# IotaWatt.net
KiCad netlist of a schematic drawn in EAGLE
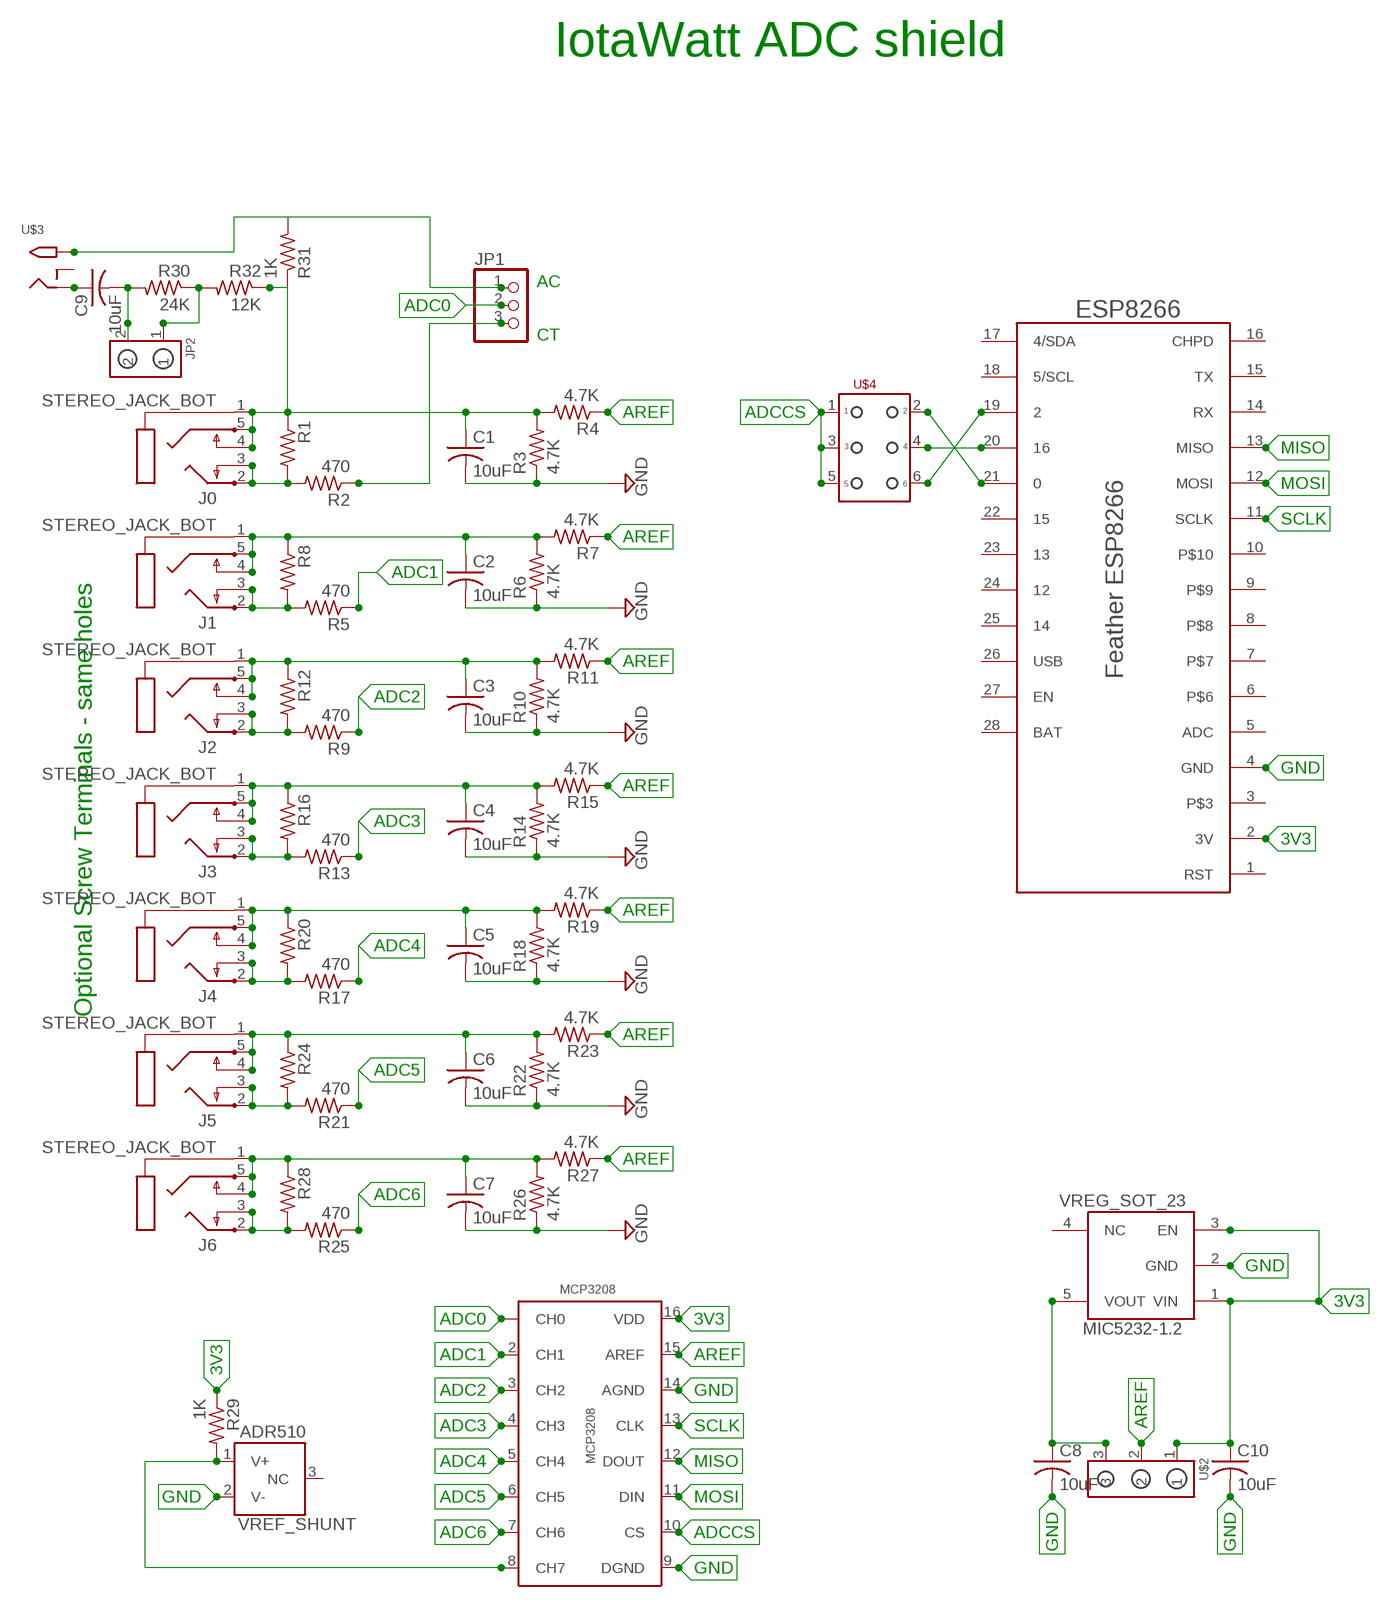
[diagram p0: schematic, sheet 1]

(export (version "E")
  (design (tool "Eeschema 10.0.6"))
  (components
    (comp (ref "ADR510")
      (value "VREF_SHUNT")
      (footprint "eagle-import:SOT23_3")
      (libsource (lib "eagle-import") (part "VREF_SHUNT"))
    )
    (comp (ref "C1")
      (value "10uF")
      (footprint "eagle-import:C0805")
      (libsource (lib "eagle-import") (part "C-USC0805"))
    )
    (comp (ref "C2")
      (value "10uF")
      (footprint "eagle-import:C0805")
      (libsource (lib "eagle-import") (part "C-USC0805"))
    )
    (comp (ref "C3")
      (value "10uF")
      (footprint "eagle-import:C0805")
      (libsource (lib "eagle-import") (part "C-USC0805"))
    )
    (comp (ref "C4")
      (value "10uF")
      (footprint "eagle-import:C0805")
      (libsource (lib "eagle-import") (part "C-USC0805"))
    )
    (comp (ref "C5")
      (value "10uF")
      (footprint "eagle-import:C0805")
      (libsource (lib "eagle-import") (part "C-USC0805"))
    )
    (comp (ref "C6")
      (value "10uF")
      (footprint "eagle-import:C0805")
      (libsource (lib "eagle-import") (part "C-USC0805"))
    )
    (comp (ref "C7")
      (value "10uF")
      (footprint "eagle-import:C0805")
      (libsource (lib "eagle-import") (part "C-USC0805"))
    )
    (comp (ref "C8")
      (value "10uF")
      (footprint "eagle-import:C0805")
      (libsource (lib "eagle-import") (part "C-USC0805"))
    )
    (comp (ref "C9")
      (value "10uF")
      (footprint "eagle-import:C0805")
      (libsource (lib "eagle-import") (part "C-USC0805"))
    )
    (comp (ref "C10")
      (value "10uF")
      (footprint "eagle-import:C0805")
      (libsource (lib "eagle-import") (part "C-USC0805"))
    )
    (comp (ref "J0")
      (value "STEREO_JACK_BOT")
      (footprint "eagle-import:STX3100")
      (libsource (lib "eagle-import") (part "STEREO_JACK_BOT"))
    )
    (comp (ref "J1")
      (value "STEREO_JACK_BOT")
      (footprint "eagle-import:STX3100")
      (libsource (lib "eagle-import") (part "STEREO_JACK_BOT"))
    )
    (comp (ref "J2")
      (value "STEREO_JACK_BOT")
      (footprint "eagle-import:STX3100")
      (libsource (lib "eagle-import") (part "STEREO_JACK_BOT"))
    )
    (comp (ref "J3")
      (value "STEREO_JACK_BOT")
      (footprint "eagle-import:STX3100")
      (libsource (lib "eagle-import") (part "STEREO_JACK_BOT"))
    )
    (comp (ref "J4")
      (value "STEREO_JACK_BOT")
      (footprint "eagle-import:STX3100")
      (libsource (lib "eagle-import") (part "STEREO_JACK_BOT"))
    )
    (comp (ref "J5")
      (value "STEREO_JACK_BOT")
      (footprint "eagle-import:STX3100")
      (libsource (lib "eagle-import") (part "STEREO_JACK_BOT"))
    )
    (comp (ref "J6")
      (value "STEREO_JACK_BOT")
      (footprint "eagle-import:STX3100")
      (libsource (lib "eagle-import") (part "STEREO_JACK_BOT"))
    )
    (comp (ref "JP1")
      (value "PINHD-1X3")
      (footprint "eagle-import:1X03")
      (libsource (lib "eagle-import") (part "PINHD-1X3"))
    )
    (comp (ref "JP2")
      (value "HEADER_1X2")
      (footprint "eagle-import:HEADER_1X2")
      (libsource (lib "eagle-import") (part "HEADER_1X2"))
    )
    (comp (ref "MCP3208")
      (value "MCP3208")
      (footprint "eagle-import:SOIC_16")
      (libsource (lib "eagle-import") (part "MCP3208"))
    )
    (comp (ref "MIC5232-1.2")
      (value "VREG_SOT_23")
      (footprint "eagle-import:SOT23_5")
      (libsource (lib "eagle-import") (part "VREG_SOT_23"))
    )
    (comp (ref "R1")
      (value "R-US_FLIPFLOP7")
      (footprint "eagle-import:0805-THM-7")
      (libsource (lib "eagle-import") (part "R-US_FLIPFLOP7"))
    )
    (comp (ref "R2")
      (value "470")
      (footprint "eagle-import:R0805")
      (libsource (lib "eagle-import") (part "R-US_R0805"))
    )
    (comp (ref "R3")
      (value "4.7K")
      (footprint "eagle-import:R0805")
      (libsource (lib "eagle-import") (part "R-US_R0805"))
    )
    (comp (ref "R4")
      (value "4.7K")
      (footprint "eagle-import:R0805")
      (libsource (lib "eagle-import") (part "R-US_R0805"))
    )
    (comp (ref "R5")
      (value "470")
      (footprint "eagle-import:R0805")
      (libsource (lib "eagle-import") (part "R-US_R0805"))
    )
    (comp (ref "R6")
      (value "4.7K")
      (footprint "eagle-import:R0805")
      (libsource (lib "eagle-import") (part "R-US_R0805"))
    )
    (comp (ref "R7")
      (value "4.7K")
      (footprint "eagle-import:R0805")
      (libsource (lib "eagle-import") (part "R-US_R0805"))
    )
    (comp (ref "R8")
      (value "R-US_FLIPFLOP7")
      (footprint "eagle-import:0805-THM-7")
      (libsource (lib "eagle-import") (part "R-US_FLIPFLOP7"))
    )
    (comp (ref "R9")
      (value "470")
      (footprint "eagle-import:R0805")
      (libsource (lib "eagle-import") (part "R-US_R0805"))
    )
    (comp (ref "R10")
      (value "4.7K")
      (footprint "eagle-import:R0805")
      (libsource (lib "eagle-import") (part "R-US_R0805"))
    )
    (comp (ref "R11")
      (value "4.7K")
      (footprint "eagle-import:R0805")
      (libsource (lib "eagle-import") (part "R-US_R0805"))
    )
    (comp (ref "R12")
      (value "R-US_FLIPFLOP7")
      (footprint "eagle-import:0805-THM-7")
      (libsource (lib "eagle-import") (part "R-US_FLIPFLOP7"))
    )
    (comp (ref "R13")
      (value "470")
      (footprint "eagle-import:R0805")
      (libsource (lib "eagle-import") (part "R-US_R0805"))
    )
    (comp (ref "R14")
      (value "4.7K")
      (footprint "eagle-import:R0805")
      (libsource (lib "eagle-import") (part "R-US_R0805"))
    )
    (comp (ref "R15")
      (value "4.7K")
      (footprint "eagle-import:R0805")
      (libsource (lib "eagle-import") (part "R-US_R0805"))
    )
    (comp (ref "R16")
      (value "R-US_FLIPFLOP7")
      (footprint "eagle-import:0805-THM-7")
      (libsource (lib "eagle-import") (part "R-US_FLIPFLOP7"))
    )
    (comp (ref "R17")
      (value "470")
      (footprint "eagle-import:R0805")
      (libsource (lib "eagle-import") (part "R-US_R0805"))
    )
    (comp (ref "R18")
      (value "4.7K")
      (footprint "eagle-import:R0805")
      (libsource (lib "eagle-import") (part "R-US_R0805"))
    )
    (comp (ref "R19")
      (value "4.7K")
      (footprint "eagle-import:R0805")
      (libsource (lib "eagle-import") (part "R-US_R0805"))
    )
    (comp (ref "R20")
      (value "R-US_FLIPFLOP7")
      (footprint "eagle-import:0805-THM-7")
      (libsource (lib "eagle-import") (part "R-US_FLIPFLOP7"))
    )
    (comp (ref "R21")
      (value "470")
      (footprint "eagle-import:R0805")
      (libsource (lib "eagle-import") (part "R-US_R0805"))
    )
    (comp (ref "R22")
      (value "4.7K")
      (footprint "eagle-import:R0805")
      (libsource (lib "eagle-import") (part "R-US_R0805"))
    )
    (comp (ref "R23")
      (value "4.7K")
      (footprint "eagle-import:R0805")
      (libsource (lib "eagle-import") (part "R-US_R0805"))
    )
    (comp (ref "R24")
      (value "R-US_FLIPFLOP7")
      (footprint "eagle-import:0805-THM-7")
      (libsource (lib "eagle-import") (part "R-US_FLIPFLOP7"))
    )
    (comp (ref "R25")
      (value "470")
      (footprint "eagle-import:R0805")
      (libsource (lib "eagle-import") (part "R-US_R0805"))
    )
    (comp (ref "R26")
      (value "4.7K")
      (footprint "eagle-import:R0805")
      (libsource (lib "eagle-import") (part "R-US_R0805"))
    )
    (comp (ref "R27")
      (value "4.7K")
      (footprint "eagle-import:R0805")
      (libsource (lib "eagle-import") (part "R-US_R0805"))
    )
    (comp (ref "R28")
      (value "R-US_FLIPFLOP7")
      (footprint "eagle-import:0805-THM-7")
      (libsource (lib "eagle-import") (part "R-US_FLIPFLOP7"))
    )
    (comp (ref "R29")
      (value "1K")
      (footprint "eagle-import:R0805")
      (libsource (lib "eagle-import") (part "R-US_R0805"))
    )
    (comp (ref "R30")
      (value "24K")
      (footprint "eagle-import:R0805")
      (libsource (lib "eagle-import") (part "R-US_R0805"))
    )
    (comp (ref "R31")
      (value "1K")
      (footprint "eagle-import:R0805")
      (libsource (lib "eagle-import") (part "R-US_R0805"))
    )
    (comp (ref "R32")
      (value "12K")
      (footprint "eagle-import:R0805")
      (libsource (lib "eagle-import") (part "R-US_R0805"))
    )
    (comp (ref "U$1")
      (value "ESP8266FEATHER")
      (footprint "eagle-import:FEATHERWING")
      (libsource (lib "eagle-import") (part "ESP8266FEATHER"))
    )
    (comp (ref "U$2")
      (value "HEADER_1X3")
      (footprint "eagle-import:HEADER_1X3")
      (libsource (lib "eagle-import") (part "HEADER_1X3"))
    )
    (comp (ref "U$3")
      (value "2.1MMJACKBOTTHM")
      (footprint "eagle-import:PJ-102A-BOT")
      (libsource (lib "eagle-import") (part "2.1MMJACKBOTTHM"))
    )
    (comp (ref "U$4")
      (value "HEADER_2X3")
      (footprint "eagle-import:HEADER_2X3")
      (libsource (lib "eagle-import") (part "HEADER_2X3"))
    )
  )
  (nets
    (net (code "1") (name "3V3") (class "Default")
      (node (ref "C10") (pin "1") (pinfunction "1_1") (pintype "passive"))
      (node (ref "MCP3208") (pin "16") (pinfunction "VDD_16") (pintype "bidirectional"))
      (node (ref "MIC5232-1.2") (pin "1") (pinfunction "VIN_1") (pintype "bidirectional"))
      (node (ref "MIC5232-1.2") (pin "3") (pinfunction "EN_3") (pintype "bidirectional"))
      (node (ref "R29") (pin "1") (pinfunction "1_1") (pintype "passive"))
      (node (ref "U$1") (pin "2") (pinfunction "3V_2") (pintype "bidirectional"))
      (node (ref "U$2") (pin "1") (pinfunction "1_1") (pintype "bidirectional"))
    )
    (net (code "2") (name "ADC0") (class "Default")
      (node (ref "JP1") (pin "2") (pinfunction "2_2") (pintype "passive"))
      (node (ref "MCP3208") (pin "1") (pinfunction "CH0_1") (pintype "input"))
    )
    (net (code "3") (name "ADC1") (class "Default")
      (node (ref "MCP3208") (pin "2") (pinfunction "CH1_2") (pintype "input"))
      (node (ref "R5") (pin "1") (pinfunction "1_1") (pintype "passive"))
    )
    (net (code "4") (name "ADC2") (class "Default")
      (node (ref "MCP3208") (pin "3") (pinfunction "CH2_3") (pintype "input"))
      (node (ref "R9") (pin "1") (pinfunction "1_1") (pintype "passive"))
    )
    (net (code "5") (name "ADC3") (class "Default")
      (node (ref "MCP3208") (pin "4") (pinfunction "CH3_4") (pintype "input"))
      (node (ref "R13") (pin "1") (pinfunction "1_1") (pintype "passive"))
    )
    (net (code "6") (name "ADC4") (class "Default")
      (node (ref "MCP3208") (pin "5") (pinfunction "CH4_5") (pintype "bidirectional"))
      (node (ref "R17") (pin "1") (pinfunction "1_1") (pintype "passive"))
    )
    (net (code "7") (name "ADC5") (class "Default")
      (node (ref "MCP3208") (pin "6") (pinfunction "CH5_6") (pintype "bidirectional"))
      (node (ref "R21") (pin "1") (pinfunction "1_1") (pintype "passive"))
    )
    (net (code "8") (name "ADC6") (class "Default")
      (node (ref "MCP3208") (pin "7") (pinfunction "CH6_7") (pintype "input"))
      (node (ref "R25") (pin "1") (pinfunction "1_1") (pintype "passive"))
    )
    (net (code "9") (name "ADCCS") (class "Default")
      (node (ref "MCP3208") (pin "10") (pinfunction "CS_10") (pintype "input"))
      (node (ref "U$4") (pin "1") (pinfunction "P$1_1") (pintype "bidirectional"))
      (node (ref "U$4") (pin "3") (pinfunction "P$3_3") (pintype "bidirectional"))
      (node (ref "U$4") (pin "5") (pinfunction "P$5_5") (pintype "bidirectional"))
    )
    (net (code "10") (name "AREF") (class "Default")
      (node (ref "MCP3208") (pin "15") (pinfunction "AREF_15") (pintype "input"))
      (node (ref "R11") (pin "1") (pinfunction "1_1") (pintype "passive"))
      (node (ref "R15") (pin "1") (pinfunction "1_1") (pintype "passive"))
      (node (ref "R19") (pin "1") (pinfunction "1_1") (pintype "passive"))
      (node (ref "R23") (pin "1") (pinfunction "1_1") (pintype "passive"))
      (node (ref "R27") (pin "1") (pinfunction "1_1") (pintype "passive"))
      (node (ref "R4") (pin "1") (pinfunction "1_1") (pintype "passive"))
      (node (ref "R7") (pin "1") (pinfunction "1_1") (pintype "passive"))
      (node (ref "U$2") (pin "2") (pinfunction "2_2") (pintype "bidirectional"))
    )
    (net (code "11") (name "GND") (class "Default")
      (node (ref "ADR510") (pin "2") (pinfunction "V-_2") (pintype "bidirectional"))
      (node (ref "C1") (pin "2") (pinfunction "2_2") (pintype "passive"))
      (node (ref "C10") (pin "2") (pinfunction "2_2") (pintype "passive"))
      (node (ref "C2") (pin "2") (pinfunction "2_2") (pintype "passive"))
      (node (ref "C3") (pin "2") (pinfunction "2_2") (pintype "passive"))
      (node (ref "C4") (pin "2") (pinfunction "2_2") (pintype "passive"))
      (node (ref "C5") (pin "2") (pinfunction "2_2") (pintype "passive"))
      (node (ref "C6") (pin "2") (pinfunction "2_2") (pintype "passive"))
      (node (ref "C7") (pin "2") (pinfunction "2_2") (pintype "passive"))
      (node (ref "C8") (pin "2") (pinfunction "2_2") (pintype "passive"))
      (node (ref "MCP3208") (pin "14") (pinfunction "AGND_14") (pintype "input"))
      (node (ref "MCP3208") (pin "9") (pinfunction "DGND_9") (pintype "bidirectional"))
      (node (ref "MIC5232-1.2") (pin "2") (pinfunction "GND_2") (pintype "bidirectional"))
      (node (ref "R10") (pin "1") (pinfunction "1_1") (pintype "passive"))
      (node (ref "R14") (pin "1") (pinfunction "1_1") (pintype "passive"))
      (node (ref "R18") (pin "1") (pinfunction "1_1") (pintype "passive"))
      (node (ref "R22") (pin "1") (pinfunction "1_1") (pintype "passive"))
      (node (ref "R26") (pin "1") (pinfunction "1_1") (pintype "passive"))
      (node (ref "R3") (pin "1") (pinfunction "1_1") (pintype "passive"))
      (node (ref "R6") (pin "1") (pinfunction "1_1") (pintype "passive"))
      (node (ref "U$1") (pin "4") (pinfunction "GND_4") (pintype "bidirectional"))
    )
    (net (code "12") (name "MISO") (class "Default")
      (node (ref "MCP3208") (pin "12") (pinfunction "DOUT_12") (pintype "bidirectional"))
      (node (ref "U$1") (pin "13") (pinfunction "MISO_13") (pintype "bidirectional"))
    )
    (net (code "13") (name "MOSI") (class "Default")
      (node (ref "MCP3208") (pin "11") (pinfunction "DIN_11") (pintype "input"))
      (node (ref "U$1") (pin "12") (pinfunction "MOSI_12") (pintype "bidirectional"))
    )
    (net (code "14") (name "Net-(ADR510-V+)") (class "Default")
      (node (ref "ADR510") (pin "1") (pinfunction "V+_1") (pintype "bidirectional"))
      (node (ref "MCP3208") (pin "8") (pinfunction "CH7_8") (pintype "bidirectional"))
      (node (ref "R29") (pin "2") (pinfunction "2_2") (pintype "passive"))
    )
    (net (code "15") (name "Net-(C9-Pad1)") (class "Default")
      (node (ref "C9") (pin "1") (pinfunction "1_1") (pintype "passive"))
      (node (ref "U$3") (pin "RING") (pinfunction "RING_RING") (pintype "bidirectional"))
    )
    (net (code "16") (name "Net-(C9-Pad2)") (class "Default")
      (node (ref "C9") (pin "2") (pinfunction "2_2") (pintype "passive"))
      (node (ref "JP2") (pin "2") (pinfunction "2_2") (pintype "bidirectional"))
      (node (ref "R30") (pin "2") (pinfunction "2_2") (pintype "passive"))
    )
    (net (code "17") (name "Net-(J0-2)") (class "Default")
      (node (ref "C1") (pin "1") (pinfunction "1_1") (pintype "passive"))
      (node (ref "J0") (pin "1") (pinfunction "1_1") (pintype "passive"))
      (node (ref "J0") (pin "4") (pinfunction "3_4") (pintype "passive"))
      (node (ref "J0") (pin "5") (pinfunction "2_5") (pintype "passive"))
      (node (ref "R1") (pin "1") (pinfunction "1_1") (pintype "passive"))
      (node (ref "R3") (pin "2") (pinfunction "2_2") (pintype "passive"))
      (node (ref "R31") (pin "1") (pinfunction "1_1") (pintype "passive"))
      (node (ref "R32") (pin "1") (pinfunction "1_1") (pintype "passive"))
      (node (ref "R4") (pin "2") (pinfunction "2_2") (pintype "passive"))
    )
    (net (code "18") (name "Net-(J0-4)") (class "Default")
      (node (ref "J0") (pin "2") (pinfunction "5_2") (pintype "passive"))
      (node (ref "J0") (pin "3") (pinfunction "4_3") (pintype "passive"))
      (node (ref "R1") (pin "2") (pinfunction "2_2") (pintype "passive"))
      (node (ref "R2") (pin "2") (pinfunction "2_2") (pintype "passive"))
    )
    (net (code "19") (name "Net-(J1-2)") (class "Default")
      (node (ref "C2") (pin "1") (pinfunction "1_1") (pintype "passive"))
      (node (ref "J1") (pin "1") (pinfunction "1_1") (pintype "passive"))
      (node (ref "J1") (pin "4") (pinfunction "3_4") (pintype "passive"))
      (node (ref "J1") (pin "5") (pinfunction "2_5") (pintype "passive"))
      (node (ref "R6") (pin "2") (pinfunction "2_2") (pintype "passive"))
      (node (ref "R7") (pin "2") (pinfunction "2_2") (pintype "passive"))
      (node (ref "R8") (pin "1") (pinfunction "1_1") (pintype "passive"))
    )
    (net (code "20") (name "Net-(J1-4)") (class "Default")
      (node (ref "J1") (pin "2") (pinfunction "5_2") (pintype "passive"))
      (node (ref "J1") (pin "3") (pinfunction "4_3") (pintype "passive"))
      (node (ref "R5") (pin "2") (pinfunction "2_2") (pintype "passive"))
      (node (ref "R8") (pin "2") (pinfunction "2_2") (pintype "passive"))
    )
    (net (code "21") (name "Net-(J2-2)") (class "Default")
      (node (ref "C3") (pin "1") (pinfunction "1_1") (pintype "passive"))
      (node (ref "J2") (pin "1") (pinfunction "1_1") (pintype "passive"))
      (node (ref "J2") (pin "4") (pinfunction "3_4") (pintype "passive"))
      (node (ref "J2") (pin "5") (pinfunction "2_5") (pintype "passive"))
      (node (ref "R10") (pin "2") (pinfunction "2_2") (pintype "passive"))
      (node (ref "R11") (pin "2") (pinfunction "2_2") (pintype "passive"))
      (node (ref "R12") (pin "1") (pinfunction "1_1") (pintype "passive"))
    )
    (net (code "22") (name "Net-(J2-4)") (class "Default")
      (node (ref "J2") (pin "2") (pinfunction "5_2") (pintype "passive"))
      (node (ref "J2") (pin "3") (pinfunction "4_3") (pintype "passive"))
      (node (ref "R12") (pin "2") (pinfunction "2_2") (pintype "passive"))
      (node (ref "R9") (pin "2") (pinfunction "2_2") (pintype "passive"))
    )
    (net (code "23") (name "Net-(J3-2)") (class "Default")
      (node (ref "C4") (pin "1") (pinfunction "1_1") (pintype "passive"))
      (node (ref "J3") (pin "1") (pinfunction "1_1") (pintype "passive"))
      (node (ref "J3") (pin "4") (pinfunction "3_4") (pintype "passive"))
      (node (ref "J3") (pin "5") (pinfunction "2_5") (pintype "passive"))
      (node (ref "R14") (pin "2") (pinfunction "2_2") (pintype "passive"))
      (node (ref "R15") (pin "2") (pinfunction "2_2") (pintype "passive"))
      (node (ref "R16") (pin "1") (pinfunction "1_1") (pintype "passive"))
    )
    (net (code "24") (name "Net-(J3-4)") (class "Default")
      (node (ref "J3") (pin "2") (pinfunction "5_2") (pintype "passive"))
      (node (ref "J3") (pin "3") (pinfunction "4_3") (pintype "passive"))
      (node (ref "R13") (pin "2") (pinfunction "2_2") (pintype "passive"))
      (node (ref "R16") (pin "2") (pinfunction "2_2") (pintype "passive"))
    )
    (net (code "25") (name "Net-(J4-2)") (class "Default")
      (node (ref "C5") (pin "1") (pinfunction "1_1") (pintype "passive"))
      (node (ref "J4") (pin "1") (pinfunction "1_1") (pintype "passive"))
      (node (ref "J4") (pin "4") (pinfunction "3_4") (pintype "passive"))
      (node (ref "J4") (pin "5") (pinfunction "2_5") (pintype "passive"))
      (node (ref "R18") (pin "2") (pinfunction "2_2") (pintype "passive"))
      (node (ref "R19") (pin "2") (pinfunction "2_2") (pintype "passive"))
      (node (ref "R20") (pin "1") (pinfunction "1_1") (pintype "passive"))
    )
    (net (code "26") (name "Net-(J4-4)") (class "Default")
      (node (ref "J4") (pin "2") (pinfunction "5_2") (pintype "passive"))
      (node (ref "J4") (pin "3") (pinfunction "4_3") (pintype "passive"))
      (node (ref "R17") (pin "2") (pinfunction "2_2") (pintype "passive"))
      (node (ref "R20") (pin "2") (pinfunction "2_2") (pintype "passive"))
    )
    (net (code "27") (name "Net-(J5-2)") (class "Default")
      (node (ref "C6") (pin "1") (pinfunction "1_1") (pintype "passive"))
      (node (ref "J5") (pin "1") (pinfunction "1_1") (pintype "passive"))
      (node (ref "J5") (pin "4") (pinfunction "3_4") (pintype "passive"))
      (node (ref "J5") (pin "5") (pinfunction "2_5") (pintype "passive"))
      (node (ref "R22") (pin "2") (pinfunction "2_2") (pintype "passive"))
      (node (ref "R23") (pin "2") (pinfunction "2_2") (pintype "passive"))
      (node (ref "R24") (pin "1") (pinfunction "1_1") (pintype "passive"))
    )
    (net (code "28") (name "Net-(J5-4)") (class "Default")
      (node (ref "J5") (pin "2") (pinfunction "5_2") (pintype "passive"))
      (node (ref "J5") (pin "3") (pinfunction "4_3") (pintype "passive"))
      (node (ref "R21") (pin "2") (pinfunction "2_2") (pintype "passive"))
      (node (ref "R24") (pin "2") (pinfunction "2_2") (pintype "passive"))
    )
    (net (code "29") (name "Net-(J6-2)") (class "Default")
      (node (ref "C7") (pin "1") (pinfunction "1_1") (pintype "passive"))
      (node (ref "J6") (pin "1") (pinfunction "1_1") (pintype "passive"))
      (node (ref "J6") (pin "4") (pinfunction "3_4") (pintype "passive"))
      (node (ref "J6") (pin "5") (pinfunction "2_5") (pintype "passive"))
      (node (ref "R26") (pin "2") (pinfunction "2_2") (pintype "passive"))
      (node (ref "R27") (pin "2") (pinfunction "2_2") (pintype "passive"))
      (node (ref "R28") (pin "1") (pinfunction "1_1") (pintype "passive"))
    )
    (net (code "30") (name "Net-(J6-4)") (class "Default")
      (node (ref "J6") (pin "2") (pinfunction "5_2") (pintype "passive"))
      (node (ref "J6") (pin "3") (pinfunction "4_3") (pintype "passive"))
      (node (ref "R25") (pin "2") (pinfunction "2_2") (pintype "passive"))
      (node (ref "R28") (pin "2") (pinfunction "2_2") (pintype "passive"))
    )
    (net (code "31") (name "Net-(JP1-Pad1)") (class "Default")
      (node (ref "JP1") (pin "1") (pinfunction "1_1") (pintype "passive"))
      (node (ref "R31") (pin "2") (pinfunction "2_2") (pintype "passive"))
      (node (ref "U$3") (pin "TIP") (pinfunction "TIP_TIP") (pintype "bidirectional"))
    )
    (net (code "32") (name "Net-(JP1-Pad3)") (class "Default")
      (node (ref "JP1") (pin "3") (pinfunction "3_3") (pintype "passive"))
      (node (ref "R2") (pin "1") (pinfunction "1_1") (pintype "passive"))
    )
    (net (code "33") (name "Net-(JP2-Pad1)") (class "Default")
      (node (ref "JP2") (pin "1") (pinfunction "1_1") (pintype "bidirectional"))
      (node (ref "R30") (pin "1") (pinfunction "1_1") (pintype "passive"))
      (node (ref "R32") (pin "2") (pinfunction "2_2") (pintype "passive"))
    )
    (net (code "34") (name "Net-(MIC5232-1.2-VOUT)") (class "Default")
      (node (ref "C8") (pin "1") (pinfunction "1_1") (pintype "passive"))
      (node (ref "MIC5232-1.2") (pin "5") (pinfunction "VOUT_5") (pintype "bidirectional"))
      (node (ref "U$2") (pin "3") (pinfunction "3_3") (pintype "bidirectional"))
    )
    (net (code "35") (name "Net-(U$1-0)") (class "Default")
      (node (ref "U$1") (pin "21") (pinfunction "0_21") (pintype "bidirectional"))
      (node (ref "U$4") (pin "2") (pinfunction "P$2_2") (pintype "bidirectional"))
    )
    (net (code "36") (name "Net-(U$1-2)") (class "Default")
      (node (ref "U$1") (pin "19") (pinfunction "2_19") (pintype "bidirectional"))
      (node (ref "U$4") (pin "6") (pinfunction "P$6_6") (pintype "bidirectional"))
    )
    (net (code "37") (name "Net-(U$1-16)") (class "Default")
      (node (ref "U$1") (pin "20") (pinfunction "16_20") (pintype "bidirectional"))
      (node (ref "U$4") (pin "4") (pinfunction "P$4_4") (pintype "bidirectional"))
    )
    (net (code "38") (name "SCLK") (class "Default")
      (node (ref "MCP3208") (pin "13") (pinfunction "CLK_13") (pintype "input"))
      (node (ref "U$1") (pin "11") (pinfunction "SCLK_11") (pintype "bidirectional"))
    )
    (net (code "39") (name "unconnected-(ADR510-NC-Pad3)") (class "Default")
      (node (ref "ADR510") (pin "3") (pinfunction "NC_3") (pintype "bidirectional"))
    )
    (net (code "40") (name "unconnected-(MIC5232-1.2-NC-Pad4)") (class "Default")
      (node (ref "MIC5232-1.2") (pin "4") (pinfunction "NC_4") (pintype "bidirectional"))
    )
    (net (code "41") (name "unconnected-(U$1-4{slash}SDA-Pad17)") (class "Default")
      (node (ref "U$1") (pin "17") (pinfunction "4/SDA_17") (pintype "bidirectional"))
    )
    (net (code "42") (name "unconnected-(U$1-5{slash}SCL-Pad18)") (class "Default")
      (node (ref "U$1") (pin "18") (pinfunction "5/SCL_18") (pintype "bidirectional"))
    )
    (net (code "43") (name "unconnected-(U$1-12-Pad24)") (class "Default")
      (node (ref "U$1") (pin "24") (pinfunction "12_24") (pintype "bidirectional"))
    )
    (net (code "44") (name "unconnected-(U$1-13-Pad23)") (class "Default")
      (node (ref "U$1") (pin "23") (pinfunction "13_23") (pintype "bidirectional"))
    )
    (net (code "45") (name "unconnected-(U$1-14-Pad25)") (class "Default")
      (node (ref "U$1") (pin "25") (pinfunction "14_25") (pintype "bidirectional"))
    )
    (net (code "46") (name "unconnected-(U$1-15-Pad22)") (class "Default")
      (node (ref "U$1") (pin "22") (pinfunction "15_22") (pintype "bidirectional"))
    )
    (net (code "47") (name "unconnected-(U$1-ADC-Pad5)") (class "Default")
      (node (ref "U$1") (pin "5") (pinfunction "ADC_5") (pintype "bidirectional"))
    )
    (net (code "48") (name "unconnected-(U$1-BAT-Pad28)") (class "Default")
      (node (ref "U$1") (pin "28") (pinfunction "BAT_28") (pintype "bidirectional"))
    )
    (net (code "49") (name "unconnected-(U$1-CHPD-Pad16)") (class "Default")
      (node (ref "U$1") (pin "16") (pinfunction "CHPD_16") (pintype "bidirectional"))
    )
    (net (code "50") (name "unconnected-(U$1-EN-Pad27)") (class "Default")
      (node (ref "U$1") (pin "27") (pinfunction "EN_27") (pintype "bidirectional"))
    )
    (net (code "51") (name "unconnected-(U$1-P$3-Pad3)") (class "Default")
      (node (ref "U$1") (pin "3") (pinfunction "P$3_3") (pintype "bidirectional"))
    )
    (net (code "52") (name "unconnected-(U$1-P$6-Pad6)") (class "Default")
      (node (ref "U$1") (pin "6") (pinfunction "P$6_6") (pintype "bidirectional"))
    )
    (net (code "53") (name "unconnected-(U$1-P$7-Pad7)") (class "Default")
      (node (ref "U$1") (pin "7") (pinfunction "P$7_7") (pintype "bidirectional"))
    )
    (net (code "54") (name "unconnected-(U$1-P$8-Pad8)") (class "Default")
      (node (ref "U$1") (pin "8") (pinfunction "P$8_8") (pintype "bidirectional"))
    )
    (net (code "55") (name "unconnected-(U$1-P$9-Pad9)") (class "Default")
      (node (ref "U$1") (pin "9") (pinfunction "P$9_9") (pintype "bidirectional"))
    )
    (net (code "56") (name "unconnected-(U$1-P$10-Pad10)") (class "Default")
      (node (ref "U$1") (pin "10") (pinfunction "P$10_10") (pintype "bidirectional"))
    )
    (net (code "57") (name "unconnected-(U$1-RST-Pad1)") (class "Default")
      (node (ref "U$1") (pin "1") (pinfunction "RST_1") (pintype "bidirectional"))
    )
    (net (code "58") (name "unconnected-(U$1-RX-Pad14)") (class "Default")
      (node (ref "U$1") (pin "14") (pinfunction "RX_14") (pintype "bidirectional"))
    )
    (net (code "59") (name "unconnected-(U$1-TX-Pad15)") (class "Default")
      (node (ref "U$1") (pin "15") (pinfunction "TX_15") (pintype "bidirectional"))
    )
    (net (code "60") (name "unconnected-(U$1-USB-Pad26)") (class "Default")
      (node (ref "U$1") (pin "26") (pinfunction "USB_26") (pintype "bidirectional"))
    )
    (net (code "61") (name "unconnected-(U$3-PadRING_SW)") (class "Default")
      (node (ref "U$3") (pin "RING_SW") (pinfunction "RING_SW_RING_SW") (pintype "bidirectional"))
    )
  )
)
